# BoardIOModule.net
KiCad netlist of a schematic drawn in Altium Designer
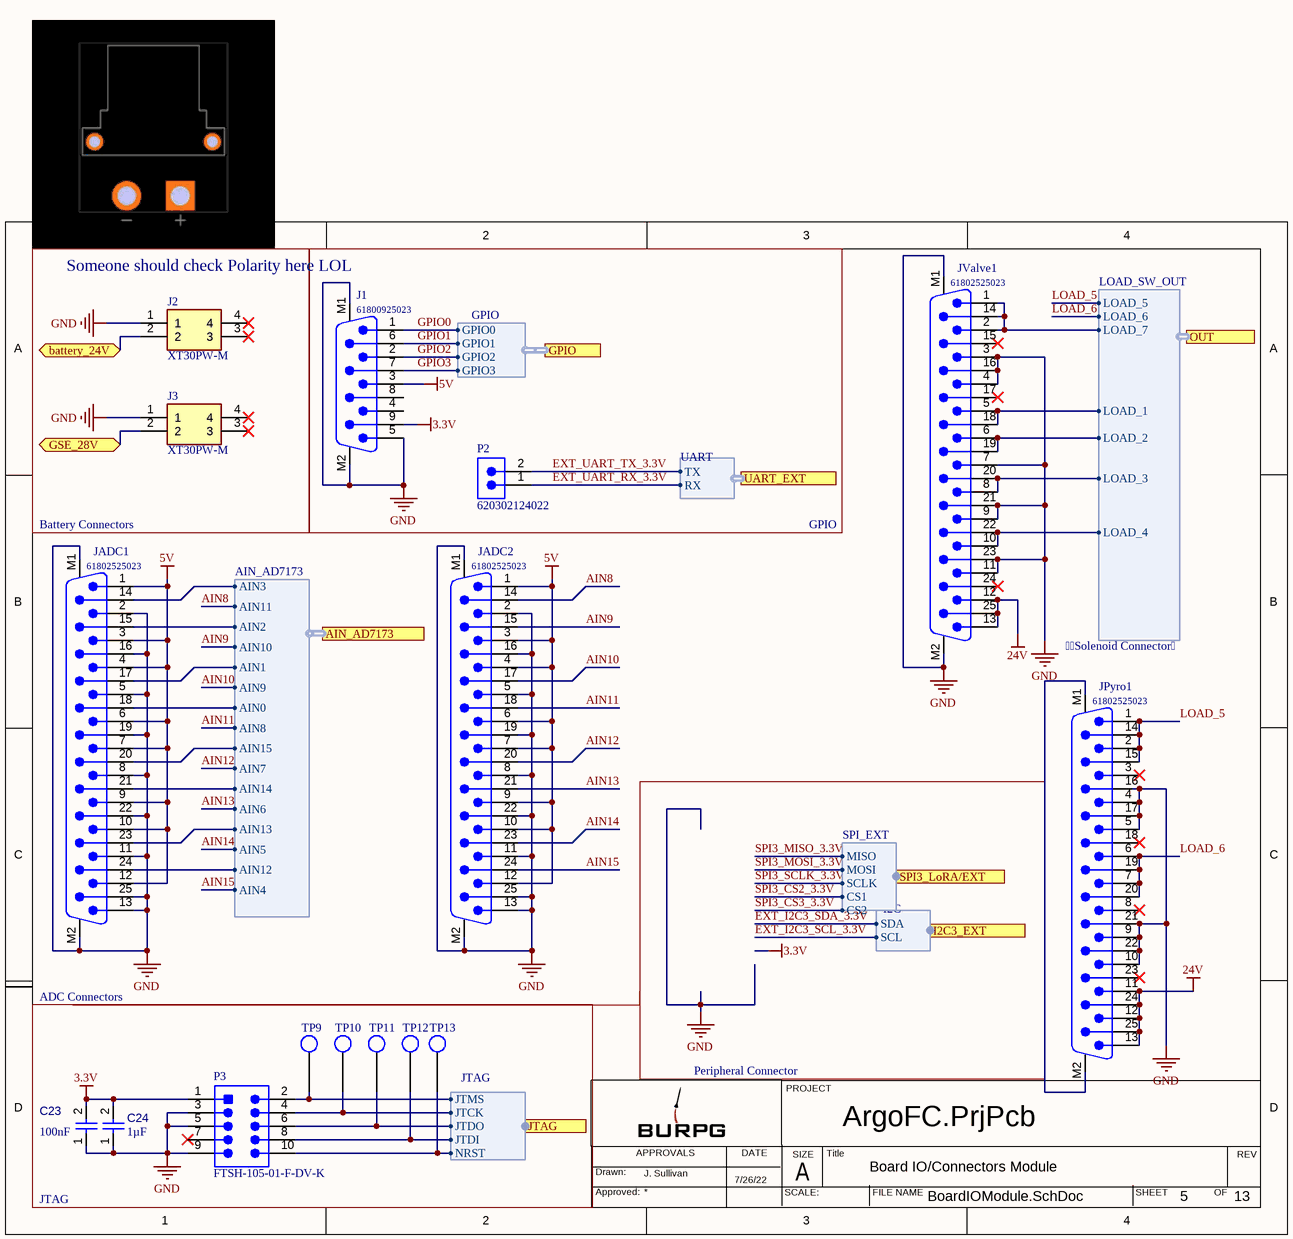
[diagram p0: BoardIOModule.SchDoc]

(export (version "E")
  (design (tool "Eeschema 10.0.6"))
  (components
    (comp (ref "C23")
      (value "100nF")
      (footprint "CAPC1005X56X25LL10T15")
      (description "Chip Capacitor, 0.1 uF, +/- 5%, 16 V, 0402 (1005 Metric)")
      (fields (field (name "TOLERANCE") "5%") (field (name "Comment") "CAP-NP-2"))
      (libsource (lib "Boston University") (part "CAP-NP-2"))
    )
    (comp (ref "C24")
      (value "1µF")
      (footprint "CAPC1608X90X35ML15T15")
      (description "Chip Capacitor, 1 uF, +/- 10%, 16 V, 0603 (1608 Metric)")
      (fields (field (name "TOLERANCE") "10%") (field (name "Comment") "CAP-NP-2"))
      (libsource (lib "Boston University") (part "CAP-NP-2"))
    )
    (comp (ref "J1")
      (value "61800925023")
      (footprint "61800925023")
      (description "Male PCB Connector WR-DSUB, Vertical, 9 pins")
      (fields (field (name "MANUFACTURER") "Wurth Elektronik") (field (name "PUBLISHER") "WurthElektronik"))
      (libsource (lib "Altium Content Vault") (part "WE-CN-2S-2M-D9"))
    )
    (comp (ref "J2")
      (value "XT30PW-M")
      (footprint "SamacSys:XT30PWM")
      (description "Connector")
      (libsource (lib "*") (part "XT30PW-M"))
    )
    (comp (ref "J3")
      (value "XT30PW-M")
      (footprint "SamacSys:XT30PWM")
      (description "Connector")
      (libsource (lib "*") (part "XT30PW-M"))
    )
    (comp (ref "JADC1")
      (value "61802525023")
      (footprint "61802525023")
      (description "Male PCB Connector WR-DSUB, Vertical, 25 pins")
      (fields (field (name "MANUFACTURER") "Wurth Elektronik") (field (name "PUBLISHER") "WurthElektronik"))
      (libsource (lib "Altium Content Vault") (part "WE-CN-2S-2M-D25"))
    )
    (comp (ref "JADC2")
      (value "61802525023")
      (footprint "61802525023")
      (description "Male PCB Connector WR-DSUB, Vertical, 25 pins")
      (fields (field (name "MANUFACTURER") "Wurth Elektronik") (field (name "PUBLISHER") "WurthElektronik"))
      (libsource (lib "Altium Content Vault") (part "WE-CN-2S-2M-D25"))
    )
    (comp (ref "JPyro1")
      (value "61802525023")
      (footprint "61802525023")
      (description "Male PCB Connector WR-DSUB, Vertical, 25 pins")
      (fields (field (name "MANUFACTURER") "Wurth Elektronik") (field (name "PUBLISHER") "WurthElektronik"))
      (libsource (lib "Altium Content Vault") (part "WE-CN-2S-2M-D25"))
    )
    (comp (ref "JValve1")
      (value "61802525023")
      (footprint "61802525023")
      (description "Male PCB Connector WR-DSUB, Vertical, 25 pins")
      (fields (field (name "MANUFACTURER") "Wurth Elektronik") (field (name "PUBLISHER") "WurthElektronik"))
      (libsource (lib "Altium Content Vault") (part "WE-CN-2S-2M-D25"))
    )
    (comp (ref "P2")
      (value "620302124022")
      (footprint "620302124022")
      (libsource (lib "Altium Content Vault") (part "Header_Male_1R_02P"))
    )
    (comp (ref "P3")
      (value "FTSH-105-01-F-DV-K")
      (footprint "SMTC-FTSH-105-01-L-DV-K_V")
      (description "Male Header, Pitch 1.27 mm, 2 x 5 Position, Height 6.12 mm, RoHS, Tube")
      (fields (field (name "MANUFACTURER") "Samtec"))
      (libsource (lib "Altium Content Vault") (part "CN-2P-M-R10"))
    )
    (comp (ref "TP9")
      (value "BURPG_TestPoint1")
      (footprint "BURPG_TestPoint1")
      (libsource (lib "BURPG_generic") (part "BURPG_TestPoint1"))
    )
    (comp (ref "TP10")
      (value "BURPG_TestPoint1")
      (footprint "BURPG_TestPoint1")
      (libsource (lib "BURPG_generic") (part "BURPG_TestPoint1"))
    )
    (comp (ref "TP11")
      (value "BURPG_TestPoint1")
      (footprint "BURPG_TestPoint1")
      (libsource (lib "BURPG_generic") (part "BURPG_TestPoint1"))
    )
    (comp (ref "TP12")
      (value "BURPG_TestPoint1")
      (footprint "BURPG_TestPoint1")
      (libsource (lib "BURPG_generic") (part "BURPG_TestPoint1"))
    )
    (comp (ref "TP13")
      (value "BURPG_TestPoint1")
      (footprint "BURPG_TestPoint1")
      (libsource (lib "BURPG_generic") (part "BURPG_TestPoint1"))
    )
  )
  (nets
    (net (code "8") (name "/AIN0") (class "Default")
      (node (ref "JADC1") (pin "18") (pinfunction "18_18") (pintype "passive"))
    )
    (net (code "9") (name "/AIN1") (class "Default")
      (node (ref "JADC1") (pin "17") (pinfunction "17_17") (pintype "passive"))
    )
    (net (code "10") (name "/AIN2") (class "Default")
      (node (ref "JADC1") (pin "15") (pinfunction "15_15") (pintype "passive"))
    )
    (net (code "11") (name "/AIN3") (class "Default")
      (node (ref "JADC1") (pin "14") (pinfunction "14_14") (pintype "passive"))
    )
    (net (code "12") (name "/AIN8") (class "Default")
      (node (ref "JADC2") (pin "14") (pinfunction "14_14") (pintype "passive"))
    )
    (net (code "13") (name "/AIN9") (class "Default")
      (node (ref "JADC2") (pin "15") (pinfunction "15_15") (pintype "passive"))
    )
    (net (code "14") (name "/AIN10") (class "Default")
      (node (ref "JADC2") (pin "17") (pinfunction "17_17") (pintype "passive"))
    )
    (net (code "15") (name "/AIN11") (class "Default")
      (node (ref "JADC2") (pin "18") (pinfunction "18_18") (pintype "passive"))
    )
    (net (code "16") (name "/AIN12") (class "Default")
      (node (ref "JADC2") (pin "20") (pinfunction "20_20") (pintype "passive"))
    )
    (net (code "17") (name "/AIN13") (class "Default")
      (node (ref "JADC2") (pin "21") (pinfunction "21_21") (pintype "passive"))
    )
    (net (code "18") (name "/AIN14") (class "Default")
      (node (ref "JADC2") (pin "23") (pinfunction "23_23") (pintype "passive"))
    )
    (net (code "19") (name "/AIN15") (class "Default")
      (node (ref "JADC2") (pin "24") (pinfunction "24_24") (pintype "passive"))
    )
    (net (code "22") (name "/EXT_UART_RX_3.3V") (class "Default")
      (node (ref "P2") (pin "1") (pinfunction "1_1") (pintype "passive"))
    )
    (net (code "23") (name "/EXT_UART_TX_3.3V") (class "Default")
      (node (ref "P2") (pin "2") (pinfunction "2_2") (pintype "passive"))
    )
    (net (code "24") (name "/GPIO0") (class "Default")
      (node (ref "J1") (pin "1") (pinfunction "1_1") (pintype "passive"))
    )
    (net (code "25") (name "/GPIO1") (class "Default")
      (node (ref "J1") (pin "6") (pinfunction "6_6") (pintype "passive"))
    )
    (net (code "26") (name "/GPIO2") (class "Default")
      (node (ref "J1") (pin "2") (pinfunction "2_2") (pintype "passive"))
    )
    (net (code "27") (name "/GPIO3") (class "Default")
      (node (ref "J1") (pin "7") (pinfunction "7_7") (pintype "passive"))
    )
    (net (code "28") (name "/GSE_28V") (class "Default")
      (node (ref "J3") (pin "2") (pinfunction "2_2") (pintype "passive"))
    )
    (net (code "29") (name "/JTCK") (class "Default")
      (node (ref "P3") (pin "4") (pinfunction "4_4") (pintype "passive"))
      (node (ref "TP10") (pin "1") (pinfunction "1_1") (pintype "passive"))
    )
    (net (code "30") (name "/JTDI") (class "Default")
      (node (ref "P3") (pin "8") (pinfunction "8_8") (pintype "passive"))
      (node (ref "TP12") (pin "1") (pinfunction "1_1") (pintype "passive"))
    )
    (net (code "31") (name "/JTDO") (class "Default")
      (node (ref "P3") (pin "6") (pinfunction "6_6") (pintype "passive"))
      (node (ref "TP11") (pin "1") (pinfunction "1_1") (pintype "passive"))
    )
    (net (code "32") (name "/JTMS") (class "Default")
      (node (ref "P3") (pin "2") (pinfunction "2_2") (pintype "passive"))
      (node (ref "TP9") (pin "1") (pinfunction "1_1") (pintype "passive"))
    )
    (net (code "33") (name "/LOAD_1") (class "Default")
      (node (ref "JValve1") (pin "18") (pinfunction "18_18") (pintype "passive"))
      (node (ref "JValve1") (pin "5") (pinfunction "5_5") (pintype "passive"))
    )
    (net (code "34") (name "/LOAD_2") (class "Default")
      (node (ref "JValve1") (pin "19") (pinfunction "19_19") (pintype "passive"))
      (node (ref "JValve1") (pin "6") (pinfunction "6_6") (pintype "passive"))
    )
    (net (code "35") (name "/LOAD_3") (class "Default")
      (node (ref "JValve1") (pin "20") (pinfunction "20_20") (pintype "passive"))
      (node (ref "JValve1") (pin "8") (pinfunction "8_8") (pintype "passive"))
    )
    (net (code "36") (name "/LOAD_4") (class "Default")
      (node (ref "JValve1") (pin "10") (pinfunction "10_10") (pintype "passive"))
      (node (ref "JValve1") (pin "22") (pinfunction "22_22") (pintype "passive"))
    )
    (net (code "37") (name "/LOAD_5") (class "Default")
      (node (ref "JPyro1") (pin "1") (pinfunction "1_1") (pintype "passive"))
      (node (ref "JPyro1") (pin "14") (pinfunction "14_14") (pintype "passive"))
      (node (ref "JPyro1") (pin "15") (pinfunction "15_15") (pintype "passive"))
      (node (ref "JPyro1") (pin "2") (pinfunction "2_2") (pintype "passive"))
    )
    (net (code "38") (name "/LOAD_6") (class "Default")
      (node (ref "JPyro1") (pin "19") (pinfunction "19_19") (pintype "passive"))
      (node (ref "JPyro1") (pin "20") (pinfunction "20_20") (pintype "passive"))
      (node (ref "JPyro1") (pin "6") (pinfunction "6_6") (pintype "passive"))
      (node (ref "JPyro1") (pin "7") (pinfunction "7_7") (pintype "passive"))
    )
    (net (code "39") (name "/LOAD_7") (class "Default")
      (node (ref "JValve1") (pin "1") (pinfunction "1_1") (pintype "passive"))
      (node (ref "JValve1") (pin "14") (pinfunction "14_14") (pintype "passive"))
      (node (ref "JValve1") (pin "2") (pinfunction "2_2") (pintype "passive"))
    )
    (net (code "40") (name "/NRST") (class "Default")
      (node (ref "P3") (pin "10") (pinfunction "10_10") (pintype "passive"))
      (node (ref "TP13") (pin "1") (pinfunction "1_1") (pintype "passive"))
    )
    (net (code "47") (name "/battery_24V") (class "Default")
      (node (ref "J2") (pin "2") (pinfunction "2_2") (pintype "passive"))
    )
    (net (code "54") (name "3.3V") (class "Default")
      (node (ref "C23") (pin "2") (pinfunction "2_2") (pintype "passive"))
      (node (ref "C24") (pin "2") (pinfunction "2_2") (pintype "passive"))
      (node (ref "J1") (pin "9") (pinfunction "9_9") (pintype "passive"))
      (node (ref "P3") (pin "1") (pinfunction "1_1") (pintype "passive"))
    )
    (net (code "55") (name "5V") (class "Default")
      (node (ref "J1") (pin "3") (pinfunction "3_3") (pintype "passive"))
      (node (ref "JADC1") (pin "1") (pinfunction "1_1") (pintype "passive"))
      (node (ref "JADC1") (pin "10") (pinfunction "10_10") (pintype "passive"))
      (node (ref "JADC1") (pin "12") (pinfunction "12_12") (pintype "passive"))
      (node (ref "JADC1") (pin "3") (pinfunction "3_3") (pintype "passive"))
      (node (ref "JADC1") (pin "4") (pinfunction "4_4") (pintype "passive"))
      (node (ref "JADC1") (pin "6") (pinfunction "6_6") (pintype "passive"))
      (node (ref "JADC1") (pin "7") (pinfunction "7_7") (pintype "passive"))
      (node (ref "JADC1") (pin "9") (pinfunction "9_9") (pintype "passive"))
      (node (ref "JADC2") (pin "1") (pinfunction "1_1") (pintype "passive"))
      (node (ref "JADC2") (pin "10") (pinfunction "10_10") (pintype "passive"))
      (node (ref "JADC2") (pin "12") (pinfunction "12_12") (pintype "passive"))
      (node (ref "JADC2") (pin "3") (pinfunction "3_3") (pintype "passive"))
      (node (ref "JADC2") (pin "4") (pinfunction "4_4") (pintype "passive"))
      (node (ref "JADC2") (pin "6") (pinfunction "6_6") (pintype "passive"))
      (node (ref "JADC2") (pin "7") (pinfunction "7_7") (pintype "passive"))
      (node (ref "JADC2") (pin "9") (pinfunction "9_9") (pintype "passive"))
    )
    (net (code "56") (name "24V") (class "Default")
      (node (ref "JPyro1") (pin "11") (pinfunction "11_11") (pintype "passive"))
      (node (ref "JPyro1") (pin "12") (pinfunction "12_12") (pintype "passive"))
      (node (ref "JPyro1") (pin "13") (pinfunction "13_13") (pintype "passive"))
      (node (ref "JPyro1") (pin "24") (pinfunction "24_24") (pintype "passive"))
      (node (ref "JPyro1") (pin "25") (pinfunction "25_25") (pintype "passive"))
      (node (ref "JValve1") (pin "12") (pinfunction "12_12") (pintype "passive"))
      (node (ref "JValve1") (pin "13") (pinfunction "13_13") (pintype "passive"))
      (node (ref "JValve1") (pin "25") (pinfunction "25_25") (pintype "passive"))
    )
    (net (code "57") (name "GND") (class "Default")
      (node (ref "C23") (pin "1") (pinfunction "1_1") (pintype "passive"))
      (node (ref "C24") (pin "1") (pinfunction "1_1") (pintype "passive"))
      (node (ref "J1") (pin "5") (pinfunction "5_5") (pintype "passive"))
      (node (ref "J1") (pin "M1") (pinfunction "M1_M1") (pintype "passive"))
      (node (ref "J1") (pin "M2") (pinfunction "M2_M2") (pintype "passive"))
      (node (ref "J2") (pin "1") (pinfunction "1_1") (pintype "passive"))
      (node (ref "J3") (pin "1") (pinfunction "1_1") (pintype "passive"))
      (node (ref "JADC1") (pin "11") (pinfunction "11_11") (pintype "passive"))
      (node (ref "JADC1") (pin "13") (pinfunction "13_13") (pintype "passive"))
      (node (ref "JADC1") (pin "16") (pinfunction "16_16") (pintype "passive"))
      (node (ref "JADC1") (pin "19") (pinfunction "19_19") (pintype "passive"))
      (node (ref "JADC1") (pin "2") (pinfunction "2_2") (pintype "passive"))
      (node (ref "JADC1") (pin "22") (pinfunction "22_22") (pintype "passive"))
      (node (ref "JADC1") (pin "25") (pinfunction "25_25") (pintype "passive"))
      (node (ref "JADC1") (pin "5") (pinfunction "5_5") (pintype "passive"))
      (node (ref "JADC1") (pin "8") (pinfunction "8_8") (pintype "passive"))
      (node (ref "JADC1") (pin "M1") (pinfunction "M1_M1") (pintype "passive"))
      (node (ref "JADC1") (pin "M2") (pinfunction "M2_M2") (pintype "passive"))
      (node (ref "JADC2") (pin "11") (pinfunction "11_11") (pintype "passive"))
      (node (ref "JADC2") (pin "13") (pinfunction "13_13") (pintype "passive"))
      (node (ref "JADC2") (pin "16") (pinfunction "16_16") (pintype "passive"))
      (node (ref "JADC2") (pin "19") (pinfunction "19_19") (pintype "passive"))
      (node (ref "JADC2") (pin "2") (pinfunction "2_2") (pintype "passive"))
      (node (ref "JADC2") (pin "22") (pinfunction "22_22") (pintype "passive"))
      (node (ref "JADC2") (pin "25") (pinfunction "25_25") (pintype "passive"))
      (node (ref "JADC2") (pin "5") (pinfunction "5_5") (pintype "passive"))
      (node (ref "JADC2") (pin "8") (pinfunction "8_8") (pintype "passive"))
      (node (ref "JADC2") (pin "M1") (pinfunction "M1_M1") (pintype "passive"))
      (node (ref "JADC2") (pin "M2") (pinfunction "M2_M2") (pintype "passive"))
      (node (ref "JPyro1") (pin "10") (pinfunction "10_10") (pintype "passive"))
      (node (ref "JPyro1") (pin "16") (pinfunction "16_16") (pintype "passive"))
      (node (ref "JPyro1") (pin "17") (pinfunction "17_17") (pintype "passive"))
      (node (ref "JPyro1") (pin "21") (pinfunction "21_21") (pintype "passive"))
      (node (ref "JPyro1") (pin "22") (pinfunction "22_22") (pintype "passive"))
      (node (ref "JPyro1") (pin "4") (pinfunction "4_4") (pintype "passive"))
      (node (ref "JPyro1") (pin "5") (pinfunction "5_5") (pintype "passive"))
      (node (ref "JPyro1") (pin "9") (pinfunction "9_9") (pintype "passive"))
      (node (ref "JValve1") (pin "11") (pinfunction "11_11") (pintype "passive"))
      (node (ref "JValve1") (pin "16") (pinfunction "16_16") (pintype "passive"))
      (node (ref "JValve1") (pin "21") (pinfunction "21_21") (pintype "passive"))
      (node (ref "JValve1") (pin "23") (pinfunction "23_23") (pintype "passive"))
      (node (ref "JValve1") (pin "3") (pinfunction "3_3") (pintype "passive"))
      (node (ref "JValve1") (pin "4") (pinfunction "4_4") (pintype "passive"))
      (node (ref "JValve1") (pin "7") (pinfunction "7_7") (pintype "passive"))
      (node (ref "JValve1") (pin "9") (pinfunction "9_9") (pintype "passive"))
      (node (ref "JValve1") (pin "M1") (pinfunction "M1_M1") (pintype "passive"))
      (node (ref "JValve1") (pin "M2") (pinfunction "M2_M2") (pintype "passive"))
      (node (ref "P3") (pin "3") (pinfunction "3_3") (pintype "passive"))
      (node (ref "P3") (pin "5") (pinfunction "5_5") (pintype "passive"))
      (node (ref "P3") (pin "9") (pinfunction "9_9") (pintype "passive"))
    )
    (net (code "58") (name "Net-(JPyro1-PadM1)") (class "Default")
      (node (ref "JPyro1") (pin "M1") (pinfunction "M1_M1") (pintype "passive"))
      (node (ref "JPyro1") (pin "M2") (pinfunction "M2_M2") (pintype "passive"))
    )
    (net (code "59") (name "unconnected-(J1-Pad4)") (class "Default")
      (node (ref "J1") (pin "4") (pinfunction "4_4") (pintype "passive"))
    )
    (net (code "60") (name "unconnected-(J1-Pad8)") (class "Default")
      (node (ref "J1") (pin "8") (pinfunction "8_8") (pintype "passive"))
    )
    (net (code "61") (name "unconnected-(J2-Pad3)") (class "Default")
      (node (ref "J2") (pin "3") (pinfunction "3_3") (pintype "passive+no_connect"))
    )
    (net (code "62") (name "unconnected-(J2-Pad4)") (class "Default")
      (node (ref "J2") (pin "4") (pinfunction "4_4") (pintype "passive+no_connect"))
    )
    (net (code "63") (name "unconnected-(J3-Pad3)") (class "Default")
      (node (ref "J3") (pin "3") (pinfunction "3_3") (pintype "passive+no_connect"))
    )
    (net (code "64") (name "unconnected-(J3-Pad4)") (class "Default")
      (node (ref "J3") (pin "4") (pinfunction "4_4") (pintype "passive+no_connect"))
    )
    (net (code "65") (name "unconnected-(JADC1-Pad20)") (class "Default")
      (node (ref "JADC1") (pin "20") (pinfunction "20_20") (pintype "passive"))
    )
    (net (code "66") (name "unconnected-(JADC1-Pad21)") (class "Default")
      (node (ref "JADC1") (pin "21") (pinfunction "21_21") (pintype "passive"))
    )
    (net (code "67") (name "unconnected-(JADC1-Pad23)") (class "Default")
      (node (ref "JADC1") (pin "23") (pinfunction "23_23") (pintype "passive"))
    )
    (net (code "68") (name "unconnected-(JADC1-Pad24)") (class "Default")
      (node (ref "JADC1") (pin "24") (pinfunction "24_24") (pintype "passive"))
    )
    (net (code "69") (name "unconnected-(JPyro1-Pad3)") (class "Default")
      (node (ref "JPyro1") (pin "3") (pinfunction "3_3") (pintype "passive+no_connect"))
    )
    (net (code "70") (name "unconnected-(JPyro1-Pad8)") (class "Default")
      (node (ref "JPyro1") (pin "8") (pinfunction "8_8") (pintype "passive+no_connect"))
    )
    (net (code "71") (name "unconnected-(JPyro1-Pad18)") (class "Default")
      (node (ref "JPyro1") (pin "18") (pinfunction "18_18") (pintype "passive+no_connect"))
    )
    (net (code "72") (name "unconnected-(JPyro1-Pad23)") (class "Default")
      (node (ref "JPyro1") (pin "23") (pinfunction "23_23") (pintype "passive+no_connect"))
    )
    (net (code "73") (name "unconnected-(JValve1-Pad15)") (class "Default")
      (node (ref "JValve1") (pin "15") (pinfunction "15_15") (pintype "passive+no_connect"))
    )
    (net (code "74") (name "unconnected-(JValve1-Pad17)") (class "Default")
      (node (ref "JValve1") (pin "17") (pinfunction "17_17") (pintype "passive+no_connect"))
    )
    (net (code "75") (name "unconnected-(JValve1-Pad24)") (class "Default")
      (node (ref "JValve1") (pin "24") (pinfunction "24_24") (pintype "passive+no_connect"))
    )
    (net (code "76") (name "unconnected-(P3-Pad7)") (class "Default")
      (node (ref "P3") (pin "7") (pinfunction "7_7") (pintype "passive+no_connect"))
    )
  )
)
